# MOTOR.net
KiCad netlist of a schematic drawn in Altium Designer
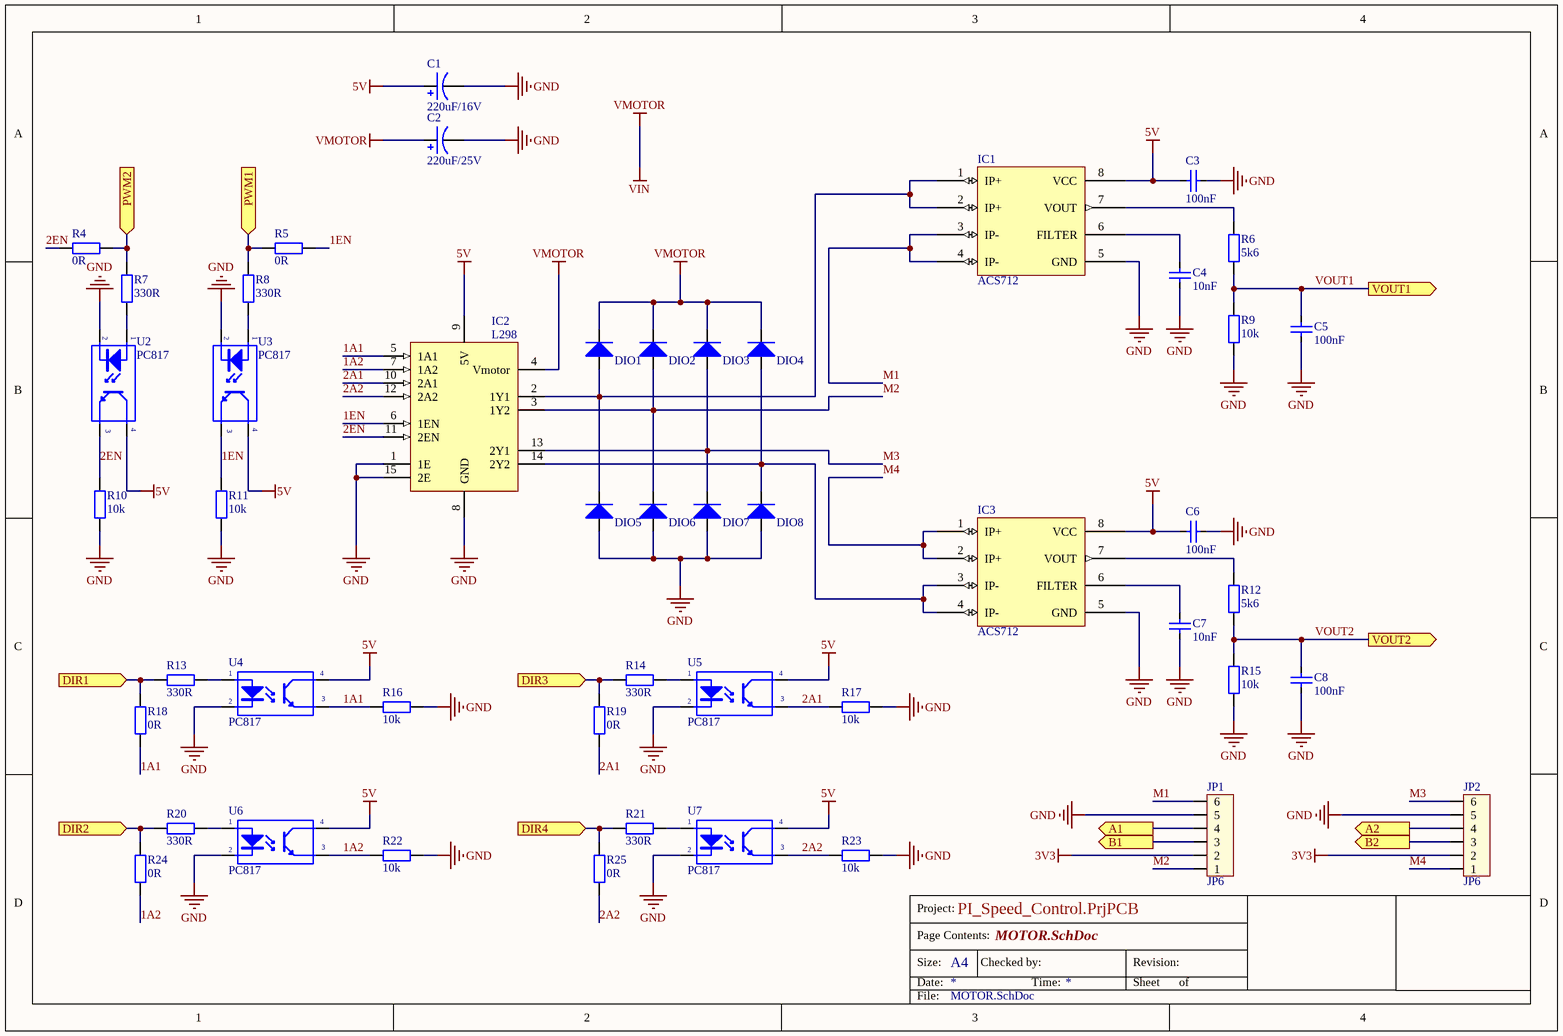
[diagram p0: MOTOR.SchDoc]

(export (version "E")
  (design (tool "Eeschema 10.0.6"))
  (components
    (comp (ref "C1")
      (value "220uF/16V")
      (footprint "C8mm")
      (description "Polarized Capacitor (Axial)")
      (fields (field (name "PUBLISHER") "Altium Limited"))
      (libsource (lib "My Library") (part "Cap Pol"))
    )
    (comp (ref "C2")
      (value "220uF/25V")
      (footprint "C8mm")
      (description "Polarized Capacitor (Axial)")
      (fields (field (name "PUBLISHER") "Altium Limited"))
      (libsource (lib "My Library") (part "Cap Pol"))
    )
    (comp (ref "C3")
      (value "100nF")
      (footprint "CAP_0805")
      (description "Capacitor")
      (fields (field (name "PUBLISHER") "Altium Limited"))
      (libsource (lib "My Library") (part "CapSMD"))
    )
    (comp (ref "C4")
      (value "10nF")
      (footprint "CAP_0805")
      (description "Capacitor")
      (fields (field (name "PUBLISHER") "Altium Limited"))
      (libsource (lib "My Library") (part "CapSMD"))
    )
    (comp (ref "C5")
      (value "100nF")
      (footprint "CAP_0805")
      (description "Capacitor")
      (fields (field (name "PUBLISHER") "Altium Limited"))
      (libsource (lib "My Library") (part "CapSMD"))
    )
    (comp (ref "C6")
      (value "100nF")
      (footprint "CAP_0805")
      (description "Capacitor")
      (fields (field (name "PUBLISHER") "Altium Limited"))
      (libsource (lib "My Library") (part "CapSMD"))
    )
    (comp (ref "C7")
      (value "10nF")
      (footprint "CAP_0805")
      (description "Capacitor")
      (fields (field (name "PUBLISHER") "Altium Limited"))
      (libsource (lib "My Library") (part "CapSMD"))
    )
    (comp (ref "C8")
      (value "100nF")
      (footprint "CAP_0805")
      (description "Capacitor")
      (fields (field (name "PUBLISHER") "Altium Limited"))
      (libsource (lib "My Library") (part "CapSMD"))
    )
    (comp (ref "DIO1")
      (value "Diode SMD")
      (footprint "DIO-214AC(SMA)")
      (description "Default Diode")
      (fields (field (name "PUBLISHER") "Altium Limited"))
      (libsource (lib "My Library") (part "Diode SMD"))
    )
    (comp (ref "DIO2")
      (value "Diode SMD")
      (footprint "DIO-214AC(SMA)")
      (description "Default Diode")
      (fields (field (name "PUBLISHER") "Altium Limited"))
      (libsource (lib "My Library") (part "Diode SMD"))
    )
    (comp (ref "DIO3")
      (value "Diode SMD")
      (footprint "DIO-214AC(SMA)")
      (description "Default Diode")
      (fields (field (name "PUBLISHER") "Altium Limited"))
      (libsource (lib "My Library") (part "Diode SMD"))
    )
    (comp (ref "DIO4")
      (value "Diode SMD")
      (footprint "DIO-214AC(SMA)")
      (description "Default Diode")
      (fields (field (name "PUBLISHER") "Altium Limited"))
      (libsource (lib "My Library") (part "Diode SMD"))
    )
    (comp (ref "DIO5")
      (value "Diode SMD")
      (footprint "DIO-214AC(SMA)")
      (description "Default Diode")
      (fields (field (name "PUBLISHER") "Altium Limited"))
      (libsource (lib "My Library") (part "Diode SMD"))
    )
    (comp (ref "DIO6")
      (value "Diode SMD")
      (footprint "DIO-214AC(SMA)")
      (description "Default Diode")
      (fields (field (name "PUBLISHER") "Altium Limited"))
      (libsource (lib "My Library") (part "Diode SMD"))
    )
    (comp (ref "DIO7")
      (value "Diode SMD")
      (footprint "DIO-214AC(SMA)")
      (description "Default Diode")
      (fields (field (name "PUBLISHER") "Altium Limited"))
      (libsource (lib "My Library") (part "Diode SMD"))
    )
    (comp (ref "DIO8")
      (value "Diode SMD")
      (footprint "DIO-214AC(SMA)")
      (description "Default Diode")
      (fields (field (name "PUBLISHER") "Altium Limited"))
      (libsource (lib "My Library") (part "Diode SMD"))
    )
    (comp (ref "IC1") (value "ACS712") (footprint "SOIC-8") (libsource (lib "My Library") (part "ACS712")))
    (comp (ref "IC2")
      (value "L298")
      (footprint "DIP15SL2")
      (description "Dual Full-H Driver")
      (fields (field (name "PUBLISHER") "Altium Limited"))
      (libsource (lib "My Library") (part "L298"))
    )
    (comp (ref "IC3") (value "ACS712") (footprint "SOIC-8") (libsource (lib "My Library") (part "ACS712")))
    (comp (ref "JP1")
      (value "JP6")
      (footprint "CON6")
      (description "Connector 6")
      (libsource (lib "My Library") (part "Con6"))
    )
    (comp (ref "JP2")
      (value "JP6")
      (footprint "CON6")
      (description "Connector 6")
      (libsource (lib "My Library") (part "Con6"))
    )
    (comp (ref "R4")
      (value "0R")
      (footprint "RES-SMD-0805")
      (description "Resistor SMD")
      (fields
        (field (name "MANUFACTURER") "Generic Components")
        (field (name "PUBLISHER") "Altium Hobart Technology Centre")
      )
      (libsource (lib "My Library") (part "Resistor - SMD"))
    )
    (comp (ref "R5")
      (value "0R")
      (footprint "RES-SMD-0805")
      (description "Resistor SMD")
      (fields
        (field (name "MANUFACTURER") "Generic Components")
        (field (name "PUBLISHER") "Altium Hobart Technology Centre")
      )
      (libsource (lib "My Library") (part "Resistor - SMD"))
    )
    (comp (ref "R6")
      (value "5k6")
      (footprint "RES-SMD-0805")
      (description "Resistor SMD")
      (fields
        (field (name "MANUFACTURER") "Generic Components")
        (field (name "PUBLISHER") "Altium Hobart Technology Centre")
      )
      (libsource (lib "My Library") (part "Resistor - SMD"))
    )
    (comp (ref "R7")
      (value "330R")
      (footprint "RES-SMD-0805")
      (description "Resistor SMD")
      (fields
        (field (name "MANUFACTURER") "Generic Components")
        (field (name "PUBLISHER") "Altium Hobart Technology Centre")
      )
      (libsource (lib "My Library") (part "Resistor - SMD"))
    )
    (comp (ref "R8")
      (value "330R")
      (footprint "RES-SMD-0805")
      (description "Resistor SMD")
      (fields
        (field (name "MANUFACTURER") "Generic Components")
        (field (name "PUBLISHER") "Altium Hobart Technology Centre")
      )
      (libsource (lib "My Library") (part "Resistor - SMD"))
    )
    (comp (ref "R9")
      (value "10k")
      (footprint "RES-SMD-0805")
      (description "Resistor SMD")
      (fields
        (field (name "MANUFACTURER") "Generic Components")
        (field (name "PUBLISHER") "Altium Hobart Technology Centre")
      )
      (libsource (lib "My Library") (part "Resistor - SMD"))
    )
    (comp (ref "R10")
      (value "10k")
      (footprint "RES-SMD-0805")
      (description "Resistor SMD")
      (fields
        (field (name "MANUFACTURER") "Generic Components")
        (field (name "PUBLISHER") "Altium Hobart Technology Centre")
      )
      (libsource (lib "My Library") (part "Resistor - SMD"))
    )
    (comp (ref "R11")
      (value "10k")
      (footprint "RES-SMD-0805")
      (description "Resistor SMD")
      (fields
        (field (name "MANUFACTURER") "Generic Components")
        (field (name "PUBLISHER") "Altium Hobart Technology Centre")
      )
      (libsource (lib "My Library") (part "Resistor - SMD"))
    )
    (comp (ref "R12")
      (value "5k6")
      (footprint "RES-SMD-0805")
      (description "Resistor SMD")
      (fields
        (field (name "MANUFACTURER") "Generic Components")
        (field (name "PUBLISHER") "Altium Hobart Technology Centre")
      )
      (libsource (lib "My Library") (part "Resistor - SMD"))
    )
    (comp (ref "R13")
      (value "330R")
      (footprint "RES-SMD-0805")
      (description "Resistor SMD")
      (fields
        (field (name "MANUFACTURER") "Generic Components")
        (field (name "PUBLISHER") "Altium Hobart Technology Centre")
      )
      (libsource (lib "My Library") (part "Resistor - SMD"))
    )
    (comp (ref "R14")
      (value "330R")
      (footprint "RES-SMD-0805")
      (description "Resistor SMD")
      (fields
        (field (name "MANUFACTURER") "Generic Components")
        (field (name "PUBLISHER") "Altium Hobart Technology Centre")
      )
      (libsource (lib "My Library") (part "Resistor - SMD"))
    )
    (comp (ref "R15")
      (value "10k")
      (footprint "RES-SMD-0805")
      (description "Resistor SMD")
      (fields
        (field (name "MANUFACTURER") "Generic Components")
        (field (name "PUBLISHER") "Altium Hobart Technology Centre")
      )
      (libsource (lib "My Library") (part "Resistor - SMD"))
    )
    (comp (ref "R16")
      (value "10k")
      (footprint "RES-SMD-0805")
      (description "Resistor SMD")
      (fields
        (field (name "MANUFACTURER") "Generic Components")
        (field (name "PUBLISHER") "Altium Hobart Technology Centre")
      )
      (libsource (lib "My Library") (part "Resistor - SMD"))
    )
    (comp (ref "R17")
      (value "10k")
      (footprint "RES-SMD-0805")
      (description "Resistor SMD")
      (fields
        (field (name "MANUFACTURER") "Generic Components")
        (field (name "PUBLISHER") "Altium Hobart Technology Centre")
      )
      (libsource (lib "My Library") (part "Resistor - SMD"))
    )
    (comp (ref "R18")
      (value "0R")
      (footprint "RES-SMD-0805")
      (description "Resistor SMD")
      (fields
        (field (name "MANUFACTURER") "Generic Components")
        (field (name "PUBLISHER") "Altium Hobart Technology Centre")
      )
      (libsource (lib "My Library") (part "Resistor - SMD"))
    )
    (comp (ref "R19")
      (value "0R")
      (footprint "RES-SMD-0805")
      (description "Resistor SMD")
      (fields
        (field (name "MANUFACTURER") "Generic Components")
        (field (name "PUBLISHER") "Altium Hobart Technology Centre")
      )
      (libsource (lib "My Library") (part "Resistor - SMD"))
    )
    (comp (ref "R20")
      (value "330R")
      (footprint "RES-SMD-0805")
      (description "Resistor SMD")
      (fields
        (field (name "MANUFACTURER") "Generic Components")
        (field (name "PUBLISHER") "Altium Hobart Technology Centre")
      )
      (libsource (lib "My Library") (part "Resistor - SMD"))
    )
    (comp (ref "R21")
      (value "330R")
      (footprint "RES-SMD-0805")
      (description "Resistor SMD")
      (fields
        (field (name "MANUFACTURER") "Generic Components")
        (field (name "PUBLISHER") "Altium Hobart Technology Centre")
      )
      (libsource (lib "My Library") (part "Resistor - SMD"))
    )
    (comp (ref "R22")
      (value "10k")
      (footprint "RES-SMD-0805")
      (description "Resistor SMD")
      (fields
        (field (name "MANUFACTURER") "Generic Components")
        (field (name "PUBLISHER") "Altium Hobart Technology Centre")
      )
      (libsource (lib "My Library") (part "Resistor - SMD"))
    )
    (comp (ref "R23")
      (value "10k")
      (footprint "RES-SMD-0805")
      (description "Resistor SMD")
      (fields
        (field (name "MANUFACTURER") "Generic Components")
        (field (name "PUBLISHER") "Altium Hobart Technology Centre")
      )
      (libsource (lib "My Library") (part "Resistor - SMD"))
    )
    (comp (ref "R24")
      (value "0R")
      (footprint "RES-SMD-0805")
      (description "Resistor SMD")
      (fields
        (field (name "MANUFACTURER") "Generic Components")
        (field (name "PUBLISHER") "Altium Hobart Technology Centre")
      )
      (libsource (lib "My Library") (part "Resistor - SMD"))
    )
    (comp (ref "R25")
      (value "0R")
      (footprint "RES-SMD-0805")
      (description "Resistor SMD")
      (fields
        (field (name "MANUFACTURER") "Generic Components")
        (field (name "PUBLISHER") "Altium Hobart Technology Centre")
      )
      (libsource (lib "My Library") (part "Resistor - SMD"))
    )
    (comp (ref "U2")
      (value "PC817")
      (footprint "OPTO_SMD")
      (description "Single Opto")
      (libsource (lib "My Library") (part "PC817"))
    )
    (comp (ref "U3")
      (value "PC817")
      (footprint "OPTO_SMD")
      (description "Single Opto")
      (libsource (lib "My Library") (part "PC817"))
    )
    (comp (ref "U4")
      (value "PC817")
      (footprint "OPTO_SMD")
      (description "Single Opto")
      (libsource (lib "My Library") (part "PC817"))
    )
    (comp (ref "U5")
      (value "PC817")
      (footprint "OPTO_SMD")
      (description "Single Opto")
      (libsource (lib "My Library") (part "PC817"))
    )
    (comp (ref "U6")
      (value "PC817")
      (footprint "OPTO_SMD")
      (description "Single Opto")
      (libsource (lib "My Library") (part "PC817"))
    )
    (comp (ref "U7")
      (value "PC817")
      (footprint "OPTO_SMD")
      (description "Single Opto")
      (libsource (lib "My Library") (part "PC817"))
    )
  )
  (nets
    (net (code "1") (name "/1A1") (class "Default")
      (node (ref "IC2") (pin "5") (pinfunction "1A1_5") (pintype "input"))
      (node (ref "R16") (pin "1") (pinfunction "1_1") (pintype "passive"))
      (node (ref "R18") (pin "1") (pinfunction "1_1") (pintype "passive"))
      (node (ref "U4") (pin "3") (pinfunction "E_3") (pintype "passive"))
    )
    (net (code "2") (name "/1A2") (class "Default")
      (node (ref "IC2") (pin "7") (pinfunction "1A2_7") (pintype "input"))
      (node (ref "R22") (pin "1") (pinfunction "1_1") (pintype "passive"))
      (node (ref "R24") (pin "1") (pinfunction "1_1") (pintype "passive"))
      (node (ref "U6") (pin "3") (pinfunction "E_3") (pintype "passive"))
    )
    (net (code "3") (name "/1EN") (class "Default")
      (node (ref "IC2") (pin "6") (pinfunction "1EN_6") (pintype "input"))
      (node (ref "R11") (pin "1") (pinfunction "1_1") (pintype "passive"))
      (node (ref "R5") (pin "1") (pinfunction "1_1") (pintype "passive"))
      (node (ref "U3") (pin "3") (pinfunction "E_3") (pintype "passive"))
    )
    (net (code "4") (name "/2A1") (class "Default")
      (node (ref "IC2") (pin "10") (pinfunction "2A1_10") (pintype "input"))
      (node (ref "R17") (pin "1") (pinfunction "1_1") (pintype "passive"))
      (node (ref "R19") (pin "1") (pinfunction "1_1") (pintype "passive"))
      (node (ref "U5") (pin "3") (pinfunction "E_3") (pintype "passive"))
    )
    (net (code "5") (name "/2A2") (class "Default")
      (node (ref "IC2") (pin "12") (pinfunction "2A2_12") (pintype "input"))
      (node (ref "R23") (pin "1") (pinfunction "1_1") (pintype "passive"))
      (node (ref "R25") (pin "1") (pinfunction "1_1") (pintype "passive"))
      (node (ref "U7") (pin "3") (pinfunction "E_3") (pintype "passive"))
    )
    (net (code "6") (name "/2EN") (class "Default")
      (node (ref "IC2") (pin "11") (pinfunction "2EN_11") (pintype "input"))
      (node (ref "R10") (pin "1") (pinfunction "1_1") (pintype "passive"))
      (node (ref "R4") (pin "1") (pinfunction "1_1") (pintype "passive"))
      (node (ref "U2") (pin "3") (pinfunction "E_3") (pintype "passive"))
    )
    (net (code "7") (name "/A1") (class "Default")
      (node (ref "JP1") (pin "4") (pinfunction "4_4") (pintype "passive"))
    )
    (net (code "8") (name "/A2") (class "Default")
      (node (ref "JP2") (pin "4") (pinfunction "4_4") (pintype "passive"))
    )
    (net (code "9") (name "/B1") (class "Default")
      (node (ref "JP1") (pin "3") (pinfunction "3_3") (pintype "passive"))
    )
    (net (code "10") (name "/B2") (class "Default")
      (node (ref "JP2") (pin "3") (pinfunction "3_3") (pintype "passive"))
    )
    (net (code "11") (name "/DIR1") (class "Default")
      (node (ref "R13") (pin "1") (pinfunction "1_1") (pintype "passive"))
      (node (ref "R18") (pin "2") (pinfunction "2_2") (pintype "passive"))
    )
    (net (code "12") (name "/DIR2") (class "Default")
      (node (ref "R20") (pin "1") (pinfunction "1_1") (pintype "passive"))
      (node (ref "R24") (pin "2") (pinfunction "2_2") (pintype "passive"))
    )
    (net (code "13") (name "/DIR3") (class "Default")
      (node (ref "R14") (pin "1") (pinfunction "1_1") (pintype "passive"))
      (node (ref "R19") (pin "2") (pinfunction "2_2") (pintype "passive"))
    )
    (net (code "14") (name "/DIR4") (class "Default")
      (node (ref "R21") (pin "1") (pinfunction "1_1") (pintype "passive"))
      (node (ref "R25") (pin "2") (pinfunction "2_2") (pintype "passive"))
    )
    (net (code "15") (name "/M1") (class "Default")
      (node (ref "IC1") (pin "3") (pinfunction "IP-_3") (pintype "bidirectional"))
      (node (ref "IC1") (pin "4") (pinfunction "IP-_4") (pintype "bidirectional"))
      (node (ref "JP1") (pin "6") (pinfunction "6_6") (pintype "passive"))
    )
    (net (code "16") (name "/M2") (class "Default")
      (node (ref "DIO2") (pin "1") (pinfunction "A_1") (pintype "passive"))
      (node (ref "DIO6") (pin "2") (pinfunction "K_2") (pintype "passive"))
      (node (ref "IC2") (pin "3") (pinfunction "1Y2_3") (pintype "tri_state"))
      (node (ref "JP1") (pin "1") (pinfunction "1_1") (pintype "passive"))
    )
    (net (code "17") (name "/M3") (class "Default")
      (node (ref "DIO3") (pin "1") (pinfunction "A_1") (pintype "passive"))
      (node (ref "DIO7") (pin "2") (pinfunction "K_2") (pintype "passive"))
      (node (ref "IC2") (pin "13") (pinfunction "2Y1_13") (pintype "tri_state"))
      (node (ref "JP2") (pin "6") (pinfunction "6_6") (pintype "passive"))
    )
    (net (code "18") (name "/M4") (class "Default")
      (node (ref "IC3") (pin "1") (pinfunction "IP+_1") (pintype "bidirectional"))
      (node (ref "IC3") (pin "2") (pinfunction "IP+_2") (pintype "bidirectional"))
      (node (ref "JP2") (pin "1") (pinfunction "1_1") (pintype "passive"))
    )
    (net (code "19") (name "/PWM1") (class "Default")
      (node (ref "R5") (pin "2") (pinfunction "2_2") (pintype "passive"))
      (node (ref "R8") (pin "2") (pinfunction "2_2") (pintype "passive"))
    )
    (net (code "20") (name "/PWM2") (class "Default")
      (node (ref "R4") (pin "2") (pinfunction "2_2") (pintype "passive"))
      (node (ref "R7") (pin "2") (pinfunction "2_2") (pintype "passive"))
    )
    (net (code "21") (name "/VOUT1") (class "Default")
      (node (ref "C5") (pin "2") (pinfunction "2_2") (pintype "passive"))
      (node (ref "R6") (pin "2") (pinfunction "2_2") (pintype "passive"))
      (node (ref "R9") (pin "1") (pinfunction "1_1") (pintype "passive"))
    )
    (net (code "22") (name "/VOUT2") (class "Default")
      (node (ref "C8") (pin "2") (pinfunction "2_2") (pintype "passive"))
      (node (ref "R12") (pin "2") (pinfunction "2_2") (pintype "passive"))
      (node (ref "R15") (pin "1") (pinfunction "1_1") (pintype "passive"))
    )
    (net (code "23") (name "3V3") (class "Default")
      (node (ref "JP1") (pin "2") (pinfunction "2_2") (pintype "passive"))
      (node (ref "JP2") (pin "2") (pinfunction "2_2") (pintype "passive"))
    )
    (net (code "24") (name "5V") (class "Default")
      (node (ref "C1") (pin "1") (pinfunction "1_1") (pintype "passive"))
      (node (ref "C3") (pin "2") (pinfunction "2_2") (pintype "passive"))
      (node (ref "C6") (pin "2") (pinfunction "2_2") (pintype "passive"))
      (node (ref "IC1") (pin "8") (pinfunction "VCC_8") (pintype "passive"))
      (node (ref "IC2") (pin "9") (pinfunction "5V_9") (pintype "power_in"))
      (node (ref "IC3") (pin "8") (pinfunction "VCC_8") (pintype "passive"))
      (node (ref "U2") (pin "4") (pinfunction "C_4") (pintype "passive"))
      (node (ref "U3") (pin "4") (pinfunction "C_4") (pintype "passive"))
      (node (ref "U4") (pin "4") (pinfunction "C_4") (pintype "passive"))
      (node (ref "U5") (pin "4") (pinfunction "C_4") (pintype "passive"))
      (node (ref "U6") (pin "4") (pinfunction "C_4") (pintype "passive"))
      (node (ref "U7") (pin "4") (pinfunction "C_4") (pintype "passive"))
    )
    (net (code "25") (name "GND") (class "Default")
      (node (ref "C1") (pin "2") (pinfunction "2_2") (pintype "passive"))
      (node (ref "C2") (pin "2") (pinfunction "2_2") (pintype "passive"))
      (node (ref "C3") (pin "1") (pinfunction "1_1") (pintype "passive"))
      (node (ref "C4") (pin "1") (pinfunction "1_1") (pintype "passive"))
      (node (ref "C5") (pin "1") (pinfunction "1_1") (pintype "passive"))
      (node (ref "C6") (pin "1") (pinfunction "1_1") (pintype "passive"))
      (node (ref "C7") (pin "1") (pinfunction "1_1") (pintype "passive"))
      (node (ref "C8") (pin "1") (pinfunction "1_1") (pintype "passive"))
      (node (ref "DIO5") (pin "1") (pinfunction "A_1") (pintype "passive"))
      (node (ref "DIO6") (pin "1") (pinfunction "A_1") (pintype "passive"))
      (node (ref "DIO7") (pin "1") (pinfunction "A_1") (pintype "passive"))
      (node (ref "DIO8") (pin "1") (pinfunction "A_1") (pintype "passive"))
      (node (ref "IC1") (pin "5") (pinfunction "GND_5") (pintype "passive"))
      (node (ref "IC2") (pin "1") (pinfunction "1E_1") (pintype "passive"))
      (node (ref "IC2") (pin "15") (pinfunction "2E_15") (pintype "passive"))
      (node (ref "IC2") (pin "8") (pinfunction "GND_8") (pintype "power_in"))
      (node (ref "IC3") (pin "5") (pinfunction "GND_5") (pintype "passive"))
      (node (ref "JP1") (pin "5") (pinfunction "5_5") (pintype "passive"))
      (node (ref "JP2") (pin "5") (pinfunction "5_5") (pintype "passive"))
      (node (ref "R10") (pin "2") (pinfunction "2_2") (pintype "passive"))
      (node (ref "R11") (pin "2") (pinfunction "2_2") (pintype "passive"))
      (node (ref "R15") (pin "2") (pinfunction "2_2") (pintype "passive"))
      (node (ref "R16") (pin "2") (pinfunction "2_2") (pintype "passive"))
      (node (ref "R17") (pin "2") (pinfunction "2_2") (pintype "passive"))
      (node (ref "R22") (pin "2") (pinfunction "2_2") (pintype "passive"))
      (node (ref "R23") (pin "2") (pinfunction "2_2") (pintype "passive"))
      (node (ref "R9") (pin "2") (pinfunction "2_2") (pintype "passive"))
      (node (ref "U2") (pin "2") (pinfunction "K_2") (pintype "passive"))
      (node (ref "U3") (pin "2") (pinfunction "K_2") (pintype "passive"))
      (node (ref "U4") (pin "2") (pinfunction "K_2") (pintype "passive"))
      (node (ref "U5") (pin "2") (pinfunction "K_2") (pintype "passive"))
      (node (ref "U6") (pin "2") (pinfunction "K_2") (pintype "passive"))
      (node (ref "U7") (pin "2") (pinfunction "K_2") (pintype "passive"))
    )
    (net (code "26") (name "Net-(DIO1-A)") (class "Default")
      (node (ref "DIO1") (pin "1") (pinfunction "A_1") (pintype "passive"))
      (node (ref "DIO5") (pin "2") (pinfunction "K_2") (pintype "passive"))
      (node (ref "IC1") (pin "1") (pinfunction "IP+_1") (pintype "bidirectional"))
      (node (ref "IC1") (pin "2") (pinfunction "IP+_2") (pintype "bidirectional"))
      (node (ref "IC2") (pin "2") (pinfunction "1Y1_2") (pintype "tri_state"))
    )
    (net (code "27") (name "Net-(DIO4-A)") (class "Default")
      (node (ref "DIO4") (pin "1") (pinfunction "A_1") (pintype "passive"))
      (node (ref "DIO8") (pin "2") (pinfunction "K_2") (pintype "passive"))
      (node (ref "IC2") (pin "14") (pinfunction "2Y2_14") (pintype "tri_state"))
      (node (ref "IC3") (pin "3") (pinfunction "IP-_3") (pintype "bidirectional"))
      (node (ref "IC3") (pin "4") (pinfunction "IP-_4") (pintype "bidirectional"))
    )
    (net (code "28") (name "Net-(IC1-FILTER)") (class "Default")
      (node (ref "C4") (pin "2") (pinfunction "2_2") (pintype "passive"))
      (node (ref "IC1") (pin "6") (pinfunction "FILTER_6") (pintype "passive"))
    )
    (net (code "29") (name "Net-(IC1-VOUT)") (class "Default")
      (node (ref "IC1") (pin "7") (pinfunction "VOUT_7") (pintype "output"))
      (node (ref "R6") (pin "1") (pinfunction "1_1") (pintype "passive"))
    )
    (net (code "30") (name "Net-(IC3-FILTER)") (class "Default")
      (node (ref "C7") (pin "2") (pinfunction "2_2") (pintype "passive"))
      (node (ref "IC3") (pin "6") (pinfunction "FILTER_6") (pintype "passive"))
    )
    (net (code "31") (name "Net-(IC3-VOUT)") (class "Default")
      (node (ref "IC3") (pin "7") (pinfunction "VOUT_7") (pintype "output"))
      (node (ref "R12") (pin "1") (pinfunction "1_1") (pintype "passive"))
    )
    (net (code "32") (name "Net-(U2-A)") (class "Default")
      (node (ref "R7") (pin "1") (pinfunction "1_1") (pintype "passive"))
      (node (ref "U2") (pin "1") (pinfunction "A_1") (pintype "passive"))
    )
    (net (code "33") (name "Net-(U3-A)") (class "Default")
      (node (ref "R8") (pin "1") (pinfunction "1_1") (pintype "passive"))
      (node (ref "U3") (pin "1") (pinfunction "A_1") (pintype "passive"))
    )
    (net (code "34") (name "Net-(U4-A)") (class "Default")
      (node (ref "R13") (pin "2") (pinfunction "2_2") (pintype "passive"))
      (node (ref "U4") (pin "1") (pinfunction "A_1") (pintype "passive"))
    )
    (net (code "35") (name "Net-(U5-A)") (class "Default")
      (node (ref "R14") (pin "2") (pinfunction "2_2") (pintype "passive"))
      (node (ref "U5") (pin "1") (pinfunction "A_1") (pintype "passive"))
    )
    (net (code "36") (name "Net-(U6-A)") (class "Default")
      (node (ref "R20") (pin "2") (pinfunction "2_2") (pintype "passive"))
      (node (ref "U6") (pin "1") (pinfunction "A_1") (pintype "passive"))
    )
    (net (code "37") (name "Net-(U7-A)") (class "Default")
      (node (ref "R21") (pin "2") (pinfunction "2_2") (pintype "passive"))
      (node (ref "U7") (pin "1") (pinfunction "A_1") (pintype "passive"))
    )
    (net (code "38") (name "VIN") (class "Default")
      (node (ref "C2") (pin "1") (pinfunction "1_1") (pintype "passive"))
      (node (ref "DIO1") (pin "2") (pinfunction "K_2") (pintype "passive"))
      (node (ref "DIO2") (pin "2") (pinfunction "K_2") (pintype "passive"))
      (node (ref "DIO3") (pin "2") (pinfunction "K_2") (pintype "passive"))
      (node (ref "DIO4") (pin "2") (pinfunction "K_2") (pintype "passive"))
      (node (ref "IC2") (pin "4") (pinfunction "Vmotor_4") (pintype "power_in"))
    )
  )
)
